# blink1mk3_001.net
KiCad netlist of a schematic drawn in EAGLE
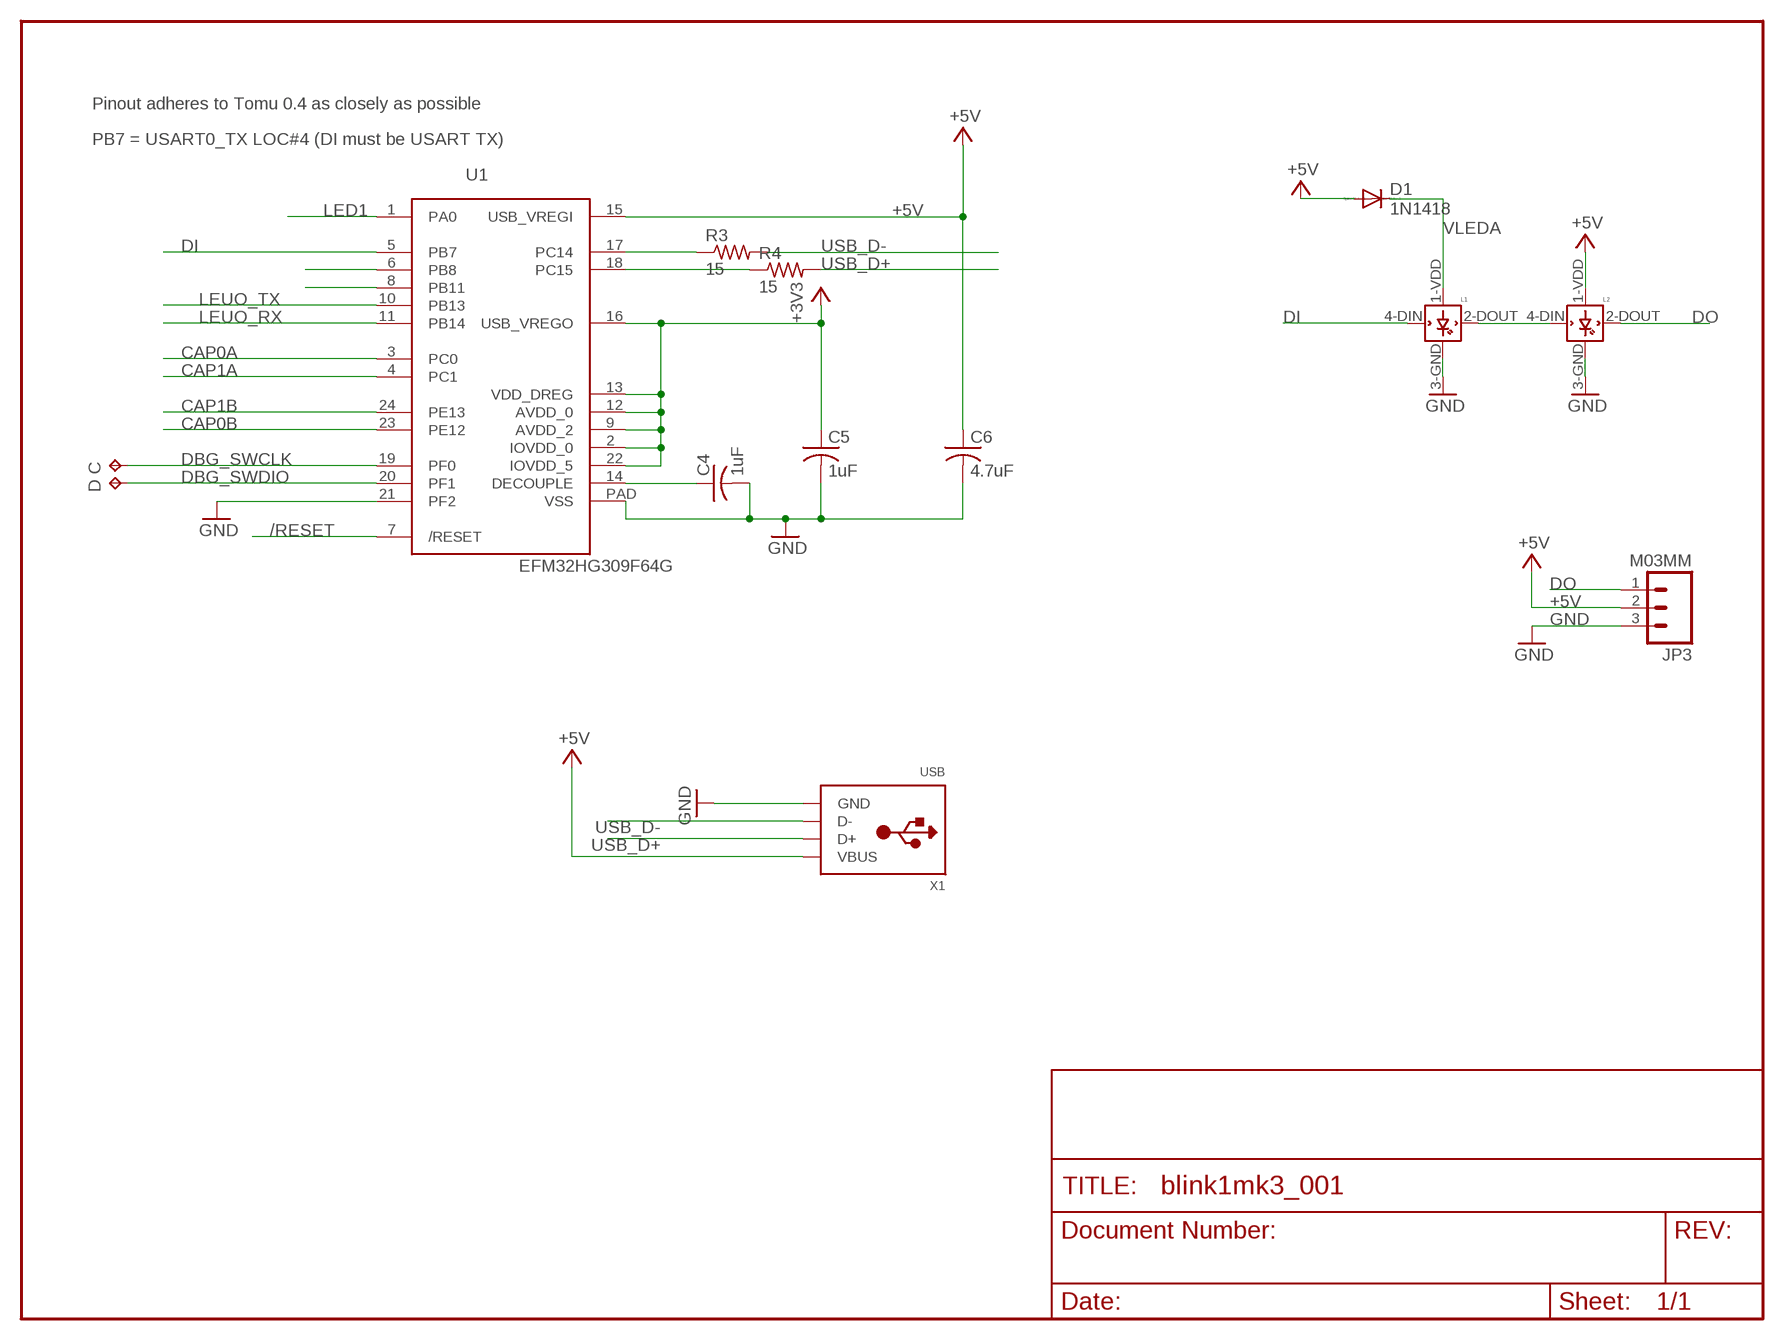
[diagram p0: schematic, sheet 1]

(export (version "E")
  (design (tool "Eeschema 10.0.6"))
  (components
    (comp (ref "C")
      (value "TPTP10R")
      (footprint "eagle-import:TP10R")
      (libsource (lib "eagle-import") (part "TPTP10R"))
    )
    (comp (ref "C4")
      (value "1uF")
      (footprint "eagle-import:C0402")
      (libsource (lib "eagle-import") (part "C-USC0402"))
    )
    (comp (ref "C5")
      (value "1uF")
      (footprint "eagle-import:C0402")
      (libsource (lib "eagle-import") (part "C-USC0402"))
    )
    (comp (ref "C6")
      (value "4.7uF")
      (footprint "eagle-import:C0402")
      (libsource (lib "eagle-import") (part "C-USC0402"))
    )
    (comp (ref "D")
      (value "TPTP10R")
      (footprint "eagle-import:TP10R")
      (libsource (lib "eagle-import") (part "TPTP10R"))
    )
    (comp (ref "D1")
      (value "1N1418")
      (footprint "eagle-import:SOD523")
      (libsource (lib "eagle-import") (part "DIODE-SOD523"))
    )
    (comp (ref "JP3")
      (value "M03MM")
      (footprint "eagle-import:1X03-1.5MM")
      (libsource (lib "eagle-import") (part "M03MM"))
    )
    (comp (ref "L1")
      (value "WS2812B")
      (footprint "eagle-import:WS2812B")
      (libsource (lib "eagle-import") (part "WS2812B"))
    )
    (comp (ref "L2")
      (value "WS2812B")
      (footprint "eagle-import:WS2812B")
      (libsource (lib "eagle-import") (part "WS2812B"))
    )
    (comp (ref "R3")
      (value "15")
      (footprint "eagle-import:R0402")
      (libsource (lib "eagle-import") (part "R-US_R0402"))
    )
    (comp (ref "R4")
      (value "15")
      (footprint "eagle-import:R0402")
      (libsource (lib "eagle-import") (part "R-US_R0402"))
    )
    (comp (ref "U1")
      (value "EFM32HG309F64G")
      (footprint "eagle-import:QFN24PAD")
      (libsource (lib "eagle-import") (part "EFM32HG309F64G"))
    )
    (comp (ref "X1")
      (value "USB")
      (footprint "eagle-import:MOLEX-48037-1000")
      (libsource (lib "eagle-import") (part "USB"))
    )
  )
  (nets
    (net (code "1") (name "+3V3") (class "Default")
      (node (ref "C5") (pin "1") (pinfunction "1_1") (pintype "passive"))
      (node (ref "U1") (pin "12") (pinfunction "AVDD_0_12") (pintype "bidirectional"))
      (node (ref "U1") (pin "13") (pinfunction "VDD_DREG_13") (pintype "bidirectional"))
      (node (ref "U1") (pin "16") (pinfunction "USB_VREGO_16") (pintype "bidirectional"))
      (node (ref "U1") (pin "2") (pinfunction "IOVDD_0_2") (pintype "bidirectional"))
      (node (ref "U1") (pin "22") (pinfunction "IOVDD_5_22") (pintype "bidirectional"))
      (node (ref "U1") (pin "9") (pinfunction "AVDD_2_9") (pintype "bidirectional"))
    )
    (net (code "2") (name "+5V") (class "Default")
      (node (ref "C6") (pin "1") (pinfunction "1_1") (pintype "passive"))
      (node (ref "D1") (pin "A") (pinfunction "A_A") (pintype "passive"))
      (node (ref "JP3") (pin "2") (pinfunction "2_2") (pintype "passive"))
      (node (ref "L2") (pin "1-VDD") (pinfunction "VDD_1-VDD") (pintype "bidirectional"))
      (node (ref "U1") (pin "15") (pinfunction "USB_VREGI_15") (pintype "bidirectional"))
      (node (ref "X1") (pin "1") (pinfunction "VBUS_1") (pintype "power_in"))
    )
    (net (code "3") (name "/CAP0A") (class "Default")
      (node (ref "U1") (pin "3") (pinfunction "PC0_3") (pintype "bidirectional"))
    )
    (net (code "4") (name "/CAP0B") (class "Default")
      (node (ref "U1") (pin "23") (pinfunction "PE12_23") (pintype "bidirectional"))
    )
    (net (code "5") (name "/CAP1A") (class "Default")
      (node (ref "U1") (pin "4") (pinfunction "PC1_4") (pintype "bidirectional"))
    )
    (net (code "6") (name "/CAP1B") (class "Default")
      (node (ref "U1") (pin "24") (pinfunction "PE13_24") (pintype "bidirectional"))
    )
    (net (code "7") (name "/DBG_SWCLK") (class "Default")
      (node (ref "C") (pin "TP") (pinfunction "TP_TP") (pintype "input"))
      (node (ref "U1") (pin "19") (pinfunction "PF0_19") (pintype "bidirectional"))
    )
    (net (code "8") (name "/DBG_SWDIO") (class "Default")
      (node (ref "D") (pin "TP") (pinfunction "TP_TP") (pintype "input"))
      (node (ref "U1") (pin "20") (pinfunction "PF1_20") (pintype "bidirectional"))
    )
    (net (code "9") (name "/DI") (class "Default")
      (node (ref "L1") (pin "4-DIN") (pinfunction "DIN_4-DIN") (pintype "input"))
      (node (ref "U1") (pin "5") (pinfunction "PB7_5") (pintype "bidirectional"))
    )
    (net (code "10") (name "/DO") (class "Default")
      (node (ref "JP3") (pin "1") (pinfunction "1_1") (pintype "passive"))
      (node (ref "L2") (pin "2-DOUT") (pinfunction "DOUT_2-DOUT") (pintype "output"))
    )
    (net (code "11") (name "/LED1") (class "Default")
      (node (ref "U1") (pin "1") (pinfunction "PA0_1") (pintype "bidirectional"))
    )
    (net (code "12") (name "/LEUO_RX") (class "Default")
      (node (ref "U1") (pin "11") (pinfunction "PB14_11") (pintype "bidirectional"))
    )
    (net (code "13") (name "/LEUO_TX") (class "Default")
      (node (ref "U1") (pin "10") (pinfunction "PB13_10") (pintype "bidirectional"))
    )
    (net (code "14") (name "/USB_D+") (class "Default")
      (node (ref "R4") (pin "2") (pinfunction "2_2") (pintype "passive"))
      (node (ref "X1") (pin "3") (pinfunction "D+_3") (pintype "bidirectional"))
    )
    (net (code "15") (name "/USB_D-") (class "Default")
      (node (ref "R3") (pin "2") (pinfunction "2_2") (pintype "passive"))
      (node (ref "X1") (pin "2") (pinfunction "D-_2") (pintype "bidirectional"))
    )
    (net (code "16") (name "/VLEDA") (class "Default")
      (node (ref "D1") (pin "C") (pinfunction "C_C") (pintype "passive"))
      (node (ref "L1") (pin "1-VDD") (pinfunction "VDD_1-VDD") (pintype "bidirectional"))
    )
    (net (code "17") (name "/{slash}RESET") (class "Default")
      (node (ref "U1") (pin "7") (pinfunction "/RESET_7") (pintype "bidirectional"))
    )
    (net (code "18") (name "GND") (class "Default")
      (node (ref "C4") (pin "2") (pinfunction "2_2") (pintype "passive"))
      (node (ref "C5") (pin "2") (pinfunction "2_2") (pintype "passive"))
      (node (ref "C6") (pin "2") (pinfunction "2_2") (pintype "passive"))
      (node (ref "JP3") (pin "3") (pinfunction "3_3") (pintype "passive"))
      (node (ref "L1") (pin "3-GND") (pinfunction "GND_3-GND") (pintype "bidirectional"))
      (node (ref "L2") (pin "3-GND") (pinfunction "GND_3-GND") (pintype "bidirectional"))
      (node (ref "U1") (pin "21") (pinfunction "PF2_21") (pintype "bidirectional"))
      (node (ref "U1") (pin "PAD") (pinfunction "VSS_PAD") (pintype "bidirectional"))
      (node (ref "X1") (pin "4") (pinfunction "GND_4") (pintype "power_in"))
    )
    (net (code "19") (name "Net-(L1-DOUT)") (class "Default")
      (node (ref "L1") (pin "2-DOUT") (pinfunction "DOUT_2-DOUT") (pintype "output"))
      (node (ref "L2") (pin "4-DIN") (pinfunction "DIN_4-DIN") (pintype "input"))
    )
    (net (code "20") (name "Net-(U1-DECOUPLE)") (class "Default")
      (node (ref "C4") (pin "1") (pinfunction "1_1") (pintype "passive"))
      (node (ref "U1") (pin "14") (pinfunction "DECOUPLE_14") (pintype "bidirectional"))
    )
    (net (code "21") (name "Net-(U1-PC14)") (class "Default")
      (node (ref "R3") (pin "1") (pinfunction "1_1") (pintype "passive"))
      (node (ref "U1") (pin "17") (pinfunction "PC14_17") (pintype "bidirectional"))
    )
    (net (code "22") (name "Net-(U1-PC15)") (class "Default")
      (node (ref "R4") (pin "1") (pinfunction "1_1") (pintype "passive"))
      (node (ref "U1") (pin "18") (pinfunction "PC15_18") (pintype "bidirectional"))
    )
    (net (code "23") (name "unconnected-(U1-PB8-Pad6)") (class "Default")
      (node (ref "U1") (pin "6") (pinfunction "PB8_6") (pintype "bidirectional"))
    )
    (net (code "24") (name "unconnected-(U1-PB11-Pad8)") (class "Default")
      (node (ref "U1") (pin "8") (pinfunction "PB11_8") (pintype "bidirectional"))
    )
  )
)
